# fg.net
KiCad netlist of a schematic drawn in EasyEDA Pro
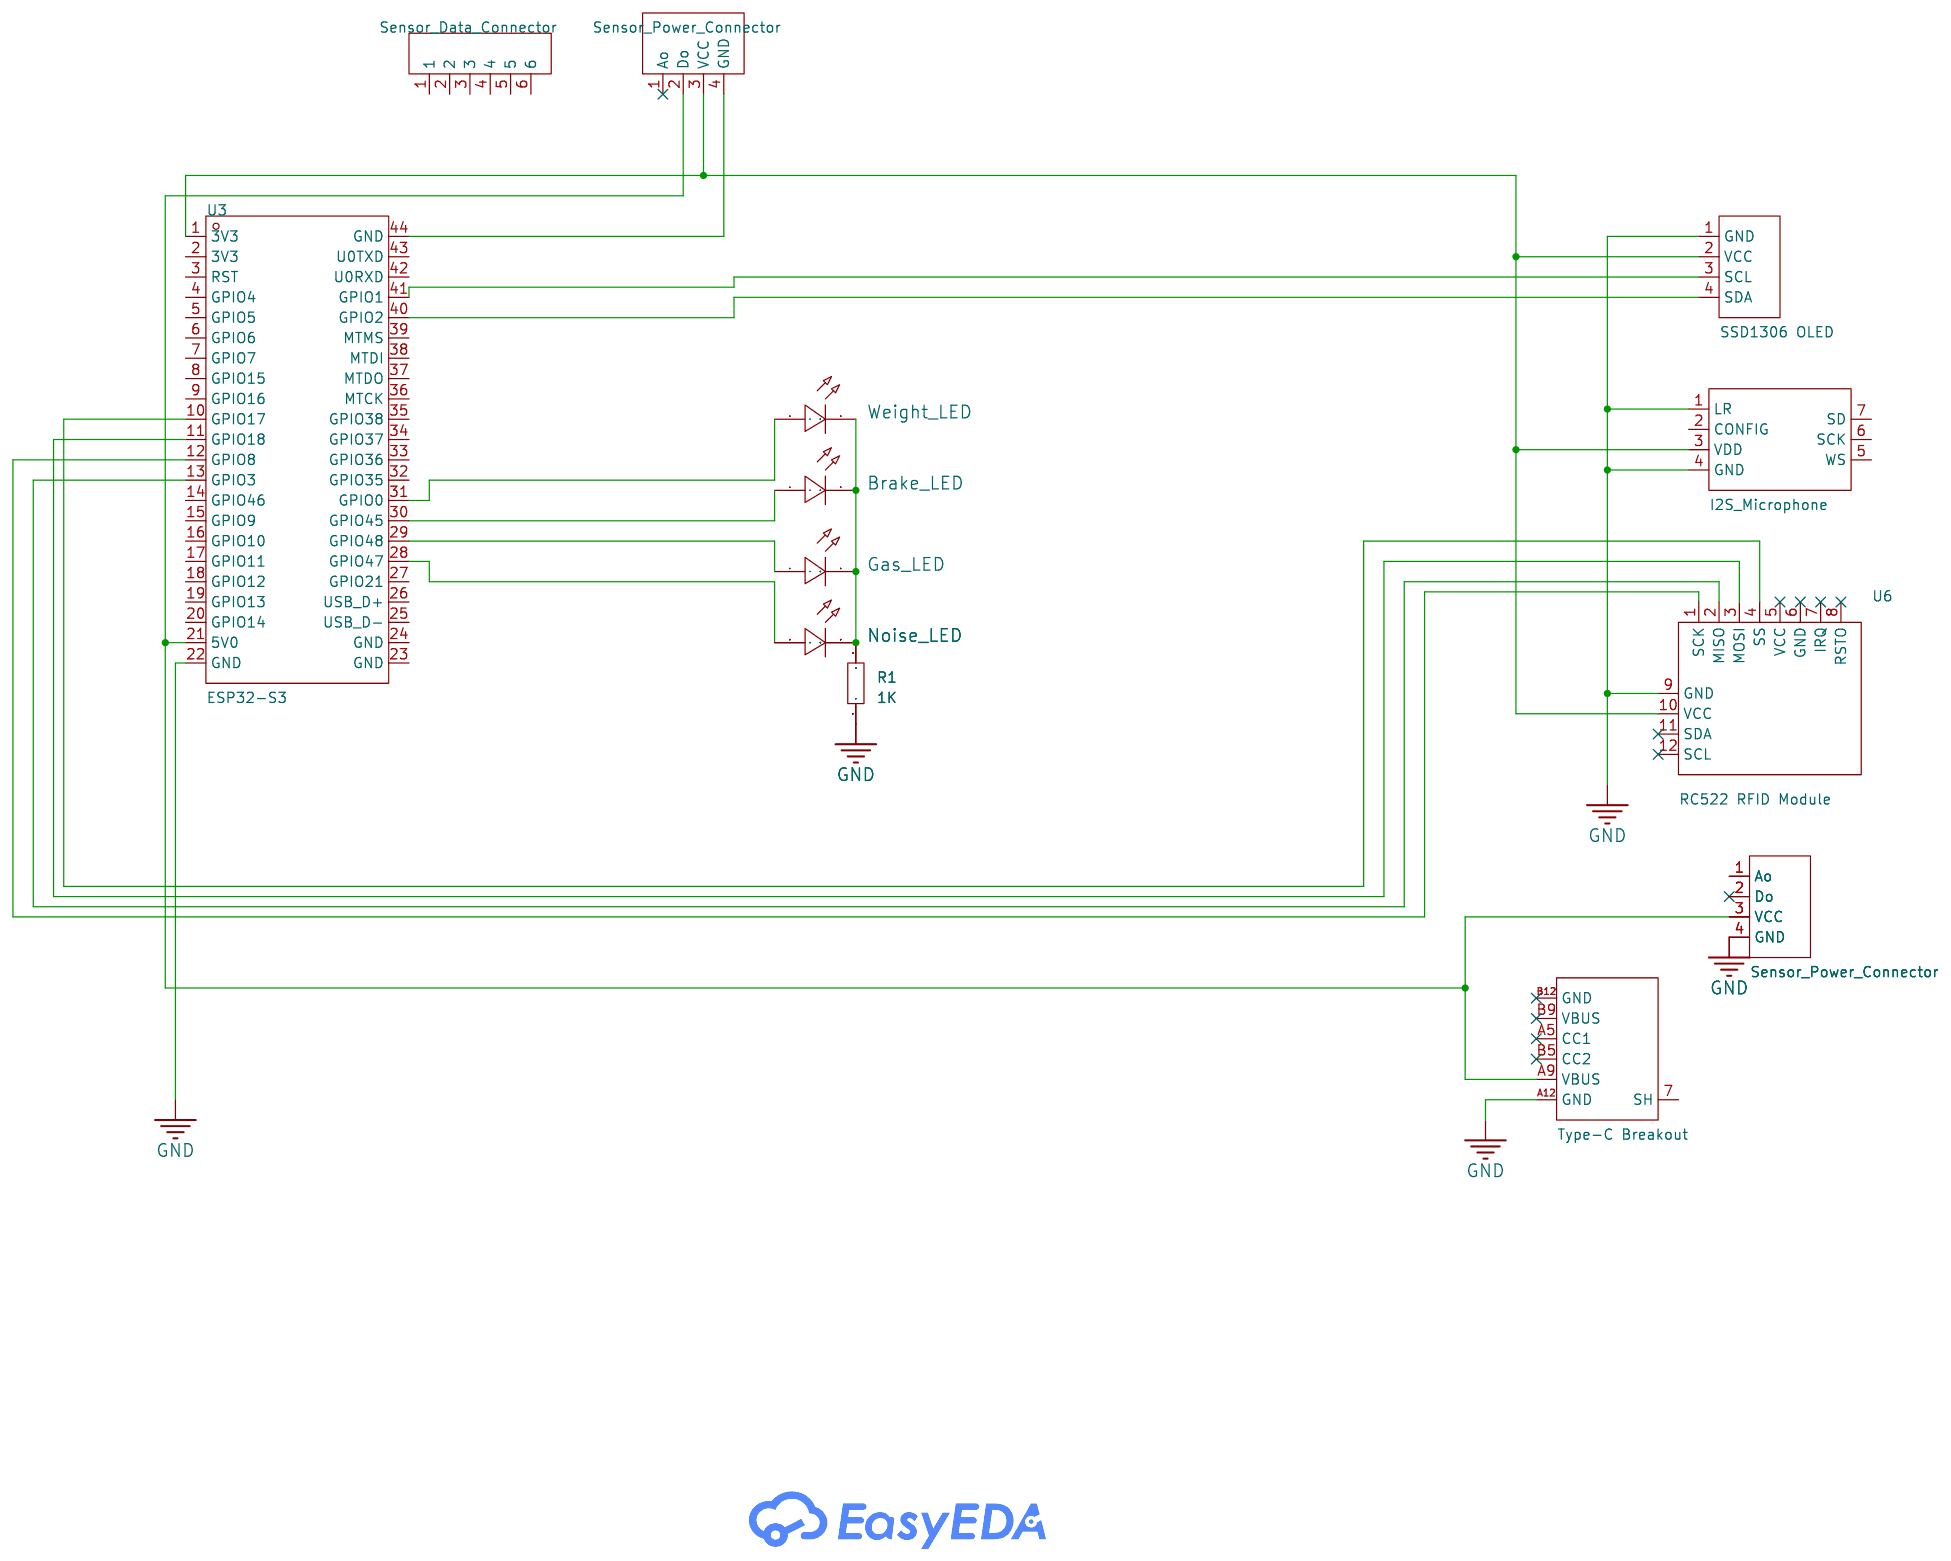
[diagram p0: schematic sheet]

(export (version "E")
  (design (tool "Eeschema 10.0.6"))
  (components
    (comp (ref "Brake_LED")
      (value "~")
      (footprint "easyedapro:LED0402-RD_YELLOW")
      (libsource (lib "easyedapro") (part "LED_R"))
    )
    (comp (ref "Display")
      (value "SSD1306 OLED")
      (footprint "easyedapro:OLED-TH_4P-L27.8-W27.3_MC096GW")
      (fields (field (name "Manufacturer Part") "MC096GW"))
      (libsource (lib "easyedapro") (part "MC096GW"))
    )
    (comp (ref "Gas_LED")
      (value "~")
      (footprint "easyedapro:LED0402-RD_YELLOW")
      (libsource (lib "easyedapro") (part "LED_R"))
    )
    (comp (ref "H1")
      (value "Sensor_Data_Connector")
      (footprint "easyedapro:HDR-TH_TW-06-01-T-S-150-085")
      (fields
        (field (name "Manufacturer Part") "TW-06-08-L-S-580-150")
        (field (name "Manufacturer") "SAMTEC")
      )
      (libsource (lib "easyedapro") (part "TW-06-08-L-S-580-150"))
    )
    (comp (ref "H2")
      (value "Sensor_Power_Connector")
      (footprint "easyedapro:HDR-TH_TW-04-06-T-S-433-120")
      (fields
        (field (name "Manufacturer Part") "TW-04-05-L-S-275-158")
        (field (name "Manufacturer") "SAMTEC")
      )
      (libsource (lib "easyedapro") (part "TW-04-05-L-S-275-158"))
    )
    (comp (ref "H3")
      (value "Sensor_Power_Connector")
      (footprint "easyedapro:HDR-TH_TW-04-06-T-S-433-120")
      (fields
        (field (name "Manufacturer Part") "TW-04-05-L-S-275-158")
        (field (name "Manufacturer") "SAMTEC")
      )
      (libsource (lib "easyedapro") (part "TW-04-05-L-S-275-158"))
    )
    (comp (ref "Noise_LED")
      (value "~")
      (footprint "easyedapro:LED0402-RD_YELLOW")
      (libsource (lib "easyedapro") (part "LED_R"))
    )
    (comp (ref "R1") (value "10K") (footprint "easyedapro:R0603") (libsource (lib "easyedapro") (part "Res")))
    (comp (ref "U3")
      (value "ESP32-S3")
      (footprint "easyedapro:COMM-TH_L63.3-W25.4-P2.54-LS22.86")
      (fields (field (name "Manufacturer Part") "ESP32-S3-DEV-KIT-N8R8"))
      (libsource (lib "easyedapro") (part "ESP32-S3-DEV-KIT-N8R8"))
    )
    (comp (ref "U5")
      (value "I2S_Microphone")
      (footprint "easyedapro:MIC-SMD_7P-L4.0-W3.0-P2.15-TL")
      (fields (field (name "Manufacturer Part") "DMM-4026-B-I2S-R") (field (name "Manufacturer") "PUIAUDIO"))
      (libsource (lib "easyedapro") (part "DMM-4026-B-I2S-R_C3171792"))
    )
    (comp (ref "U6")
      (value "RC522 RFID Module")
      (footprint "easyedapro:COMM-TH_L42.7-W40.4_PN532_NFC_RFID")
      (fields (field (name "Manufacturer Part") "PN532 NFC RFID Module v4"))
      (libsource (lib "easyedapro") (part "PN532 NFC RFID MODULE V4"))
    )
    (comp (ref "USB1")
      (value "Type-C Breakout")
      (footprint "easyedapro:USB-SMD_TYPE-C6P-ST")
      (fields (field (name "Manufacturer Part") "TCR51-65120601"))
      (libsource (lib "easyedapro") (part "TCR51-65120601"))
    )
    (comp (ref "Weight_LED")
      (value "~")
      (footprint "easyedapro:LED0402-RD_YELLOW")
      (libsource (lib "easyedapro") (part "LED_R"))
    )
  )
  (nets
    (net (code "1") (name "GND") (class "Default")
      (node (ref "Display") (pin "1") (pinfunction "GND_1") (pintype "unspecified"))
      (node (ref "H3") (pin "4") (pinfunction "GND_4") (pintype "unspecified"))
      (node (ref "R1") (pin "1") (pinfunction "1_1") (pintype "input"))
      (node (ref "U3") (pin "22") (pinfunction "GND_22") (pintype "unspecified"))
      (node (ref "U5") (pin "1") (pinfunction "LR_1") (pintype "unspecified"))
      (node (ref "U5") (pin "4") (pinfunction "GND_4") (pintype "unspecified"))
      (node (ref "U6") (pin "9") (pinfunction "GND_9") (pintype "unspecified"))
      (node (ref "USB1") (pin "A12") (pinfunction "GND_A12") (pintype "unspecified"))
    )
    (net (code "2") (name "Net-(Brake_LED-A)") (class "Default")
      (node (ref "Brake_LED") (pin "1") (pinfunction "A_1") (pintype "input"))
      (node (ref "U3") (pin "30") (pinfunction "GPIO45_30") (pintype "unspecified"))
    )
    (net (code "3") (name "Net-(Brake_LED-C)") (class "Default")
      (node (ref "Brake_LED") (pin "2") (pinfunction "C_2") (pintype "input"))
      (node (ref "Gas_LED") (pin "2") (pinfunction "C_2") (pintype "input"))
      (node (ref "Noise_LED") (pin "2") (pinfunction "C_2") (pintype "input"))
      (node (ref "R1") (pin "2") (pinfunction "2_2") (pintype "input"))
      (node (ref "Weight_LED") (pin "2") (pinfunction "C_2") (pintype "input"))
    )
    (net (code "4") (name "Net-(Display-SCL)") (class "Default")
      (node (ref "Display") (pin "3") (pinfunction "SCL_3") (pintype "unspecified"))
      (node (ref "U3") (pin "41") (pinfunction "GPIO1_41") (pintype "unspecified"))
    )
    (net (code "5") (name "Net-(Display-SDA)") (class "Default")
      (node (ref "Display") (pin "4") (pinfunction "SDA_4") (pintype "unspecified"))
      (node (ref "U3") (pin "40") (pinfunction "GPIO2_40") (pintype "unspecified"))
    )
    (net (code "6") (name "Net-(Display-VCC)") (class "Default")
      (node (ref "Display") (pin "2") (pinfunction "VCC_2") (pintype "unspecified"))
      (node (ref "H2") (pin "3") (pinfunction "VCC_3") (pintype "unspecified"))
      (node (ref "U3") (pin "1") (pinfunction "3V3_1") (pintype "unspecified"))
      (node (ref "U5") (pin "3") (pinfunction "VDD_3") (pintype "unspecified"))
      (node (ref "U6") (pin "10") (pinfunction "VCC_10") (pintype "unspecified"))
    )
    (net (code "7") (name "Net-(Gas_LED-A)") (class "Default")
      (node (ref "Gas_LED") (pin "1") (pinfunction "A_1") (pintype "input"))
      (node (ref "U3") (pin "29") (pinfunction "GPIO48_29") (pintype "unspecified"))
    )
    (net (code "8") (name "Net-(H2-Do)") (class "Default")
      (node (ref "H2") (pin "2") (pinfunction "Do_2") (pintype "unspecified"))
      (node (ref "H3") (pin "3") (pinfunction "VCC_3") (pintype "unspecified"))
      (node (ref "U3") (pin "21") (pinfunction "5V0_21") (pintype "unspecified"))
      (node (ref "USB1") (pin "A9") (pinfunction "VBUS_A9") (pintype "unspecified"))
    )
    (net (code "9") (name "Net-(H2-GND)") (class "Default")
      (node (ref "H2") (pin "4") (pinfunction "GND_4") (pintype "unspecified"))
      (node (ref "U3") (pin "44") (pinfunction "GND_44") (pintype "unspecified"))
    )
    (net (code "10") (name "Net-(Noise_LED-A)") (class "Default")
      (node (ref "Noise_LED") (pin "1") (pinfunction "A_1") (pintype "input"))
      (node (ref "U3") (pin "28") (pinfunction "GPIO47_28") (pintype "unspecified"))
    )
    (net (code "11") (name "Net-(U3-GPIO0)") (class "Default")
      (node (ref "U3") (pin "31") (pinfunction "GPIO0_31") (pintype "unspecified"))
      (node (ref "Weight_LED") (pin "1") (pinfunction "A_1") (pintype "input"))
    )
    (net (code "12") (name "Net-(U3-GPIO3)") (class "Default")
      (node (ref "U3") (pin "13") (pinfunction "GPIO3_13") (pintype "unspecified"))
      (node (ref "U6") (pin "2") (pinfunction "MISO_2") (pintype "unspecified"))
    )
    (net (code "13") (name "Net-(U3-GPIO8)") (class "Default")
      (node (ref "U3") (pin "12") (pinfunction "GPIO8_12") (pintype "unspecified"))
      (node (ref "U6") (pin "1") (pinfunction "SCK_1") (pintype "unspecified"))
    )
    (net (code "14") (name "Net-(U3-GPIO17)") (class "Default")
      (node (ref "U3") (pin "10") (pinfunction "GPIO17_10") (pintype "unspecified"))
      (node (ref "U6") (pin "4") (pinfunction "SS_4") (pintype "unspecified"))
    )
    (net (code "15") (name "Net-(U3-GPIO18)") (class "Default")
      (node (ref "U3") (pin "11") (pinfunction "GPIO18_11") (pintype "unspecified"))
      (node (ref "U6") (pin "3") (pinfunction "MOSI_3") (pintype "unspecified"))
    )
    (net (code "16") (name "unconnected-(H1-Pad1)") (class "Default")
      (node (ref "H1") (pin "1") (pinfunction "1_1") (pintype "unspecified"))
    )
    (net (code "17") (name "unconnected-(H1-Pad2)") (class "Default")
      (node (ref "H1") (pin "2") (pinfunction "2_2") (pintype "unspecified"))
    )
    (net (code "18") (name "unconnected-(H1-Pad3)") (class "Default")
      (node (ref "H1") (pin "3") (pinfunction "3_3") (pintype "unspecified"))
    )
    (net (code "19") (name "unconnected-(H1-Pad4)") (class "Default")
      (node (ref "H1") (pin "4") (pinfunction "4_4") (pintype "unspecified"))
    )
    (net (code "20") (name "unconnected-(H1-Pad5)") (class "Default")
      (node (ref "H1") (pin "5") (pinfunction "5_5") (pintype "unspecified"))
    )
    (net (code "21") (name "unconnected-(H1-Pad6)") (class "Default")
      (node (ref "H1") (pin "6") (pinfunction "6_6") (pintype "unspecified"))
    )
    (net (code "22") (name "unconnected-(H2-Ao-Pad1)") (class "Default")
      (node (ref "H2") (pin "1") (pinfunction "Ao_1") (pintype "unspecified+no_connect"))
    )
    (net (code "23") (name "unconnected-(H3-Ao-Pad1)") (class "Default")
      (node (ref "H3") (pin "1") (pinfunction "Ao_1") (pintype "unspecified"))
    )
    (net (code "24") (name "unconnected-(H3-Do-Pad2)") (class "Default")
      (node (ref "H3") (pin "2") (pinfunction "Do_2") (pintype "unspecified+no_connect"))
    )
    (net (code "25") (name "unconnected-(U3-3V3-Pad2)") (class "Default")
      (node (ref "U3") (pin "2") (pinfunction "3V3_2") (pintype "unspecified"))
    )
    (net (code "26") (name "unconnected-(U3-GND-Pad23)") (class "Default")
      (node (ref "U3") (pin "23") (pinfunction "GND_23") (pintype "unspecified"))
    )
    (net (code "27") (name "unconnected-(U3-GND-Pad24)") (class "Default")
      (node (ref "U3") (pin "24") (pinfunction "GND_24") (pintype "unspecified"))
    )
    (net (code "28") (name "unconnected-(U3-GPIO4-Pad4)") (class "Default")
      (node (ref "U3") (pin "4") (pinfunction "GPIO4_4") (pintype "unspecified"))
    )
    (net (code "29") (name "unconnected-(U3-GPIO5-Pad5)") (class "Default")
      (node (ref "U3") (pin "5") (pinfunction "GPIO5_5") (pintype "unspecified"))
    )
    (net (code "30") (name "unconnected-(U3-GPIO6-Pad6)") (class "Default")
      (node (ref "U3") (pin "6") (pinfunction "GPIO6_6") (pintype "unspecified"))
    )
    (net (code "31") (name "unconnected-(U3-GPIO7-Pad7)") (class "Default")
      (node (ref "U3") (pin "7") (pinfunction "GPIO7_7") (pintype "unspecified"))
    )
    (net (code "32") (name "unconnected-(U3-GPIO9-Pad15)") (class "Default")
      (node (ref "U3") (pin "15") (pinfunction "GPIO9_15") (pintype "unspecified"))
    )
    (net (code "33") (name "unconnected-(U3-GPIO10-Pad16)") (class "Default")
      (node (ref "U3") (pin "16") (pinfunction "GPIO10_16") (pintype "unspecified"))
    )
    (net (code "34") (name "unconnected-(U3-GPIO11-Pad17)") (class "Default")
      (node (ref "U3") (pin "17") (pinfunction "GPIO11_17") (pintype "unspecified"))
    )
    (net (code "35") (name "unconnected-(U3-GPIO12-Pad18)") (class "Default")
      (node (ref "U3") (pin "18") (pinfunction "GPIO12_18") (pintype "unspecified"))
    )
    (net (code "36") (name "unconnected-(U3-GPIO13-Pad19)") (class "Default")
      (node (ref "U3") (pin "19") (pinfunction "GPIO13_19") (pintype "unspecified"))
    )
    (net (code "37") (name "unconnected-(U3-GPIO14-Pad20)") (class "Default")
      (node (ref "U3") (pin "20") (pinfunction "GPIO14_20") (pintype "unspecified"))
    )
    (net (code "38") (name "unconnected-(U3-GPIO15-Pad8)") (class "Default")
      (node (ref "U3") (pin "8") (pinfunction "GPIO15_8") (pintype "unspecified"))
    )
    (net (code "39") (name "unconnected-(U3-GPIO16-Pad9)") (class "Default")
      (node (ref "U3") (pin "9") (pinfunction "GPIO16_9") (pintype "unspecified"))
    )
    (net (code "40") (name "unconnected-(U3-GPIO21-Pad27)") (class "Default")
      (node (ref "U3") (pin "27") (pinfunction "GPIO21_27") (pintype "unspecified"))
    )
    (net (code "41") (name "unconnected-(U3-GPIO35-Pad32)") (class "Default")
      (node (ref "U3") (pin "32") (pinfunction "GPIO35_32") (pintype "unspecified"))
    )
    (net (code "42") (name "unconnected-(U3-GPIO36-Pad33)") (class "Default")
      (node (ref "U3") (pin "33") (pinfunction "GPIO36_33") (pintype "unspecified"))
    )
    (net (code "43") (name "unconnected-(U3-GPIO37-Pad34)") (class "Default")
      (node (ref "U3") (pin "34") (pinfunction "GPIO37_34") (pintype "unspecified"))
    )
    (net (code "44") (name "unconnected-(U3-GPIO38-Pad35)") (class "Default")
      (node (ref "U3") (pin "35") (pinfunction "GPIO38_35") (pintype "unspecified"))
    )
    (net (code "45") (name "unconnected-(U3-GPIO46-Pad14)") (class "Default")
      (node (ref "U3") (pin "14") (pinfunction "GPIO46_14") (pintype "unspecified"))
    )
    (net (code "46") (name "unconnected-(U3-MTCK-Pad36)") (class "Default")
      (node (ref "U3") (pin "36") (pinfunction "MTCK_36") (pintype "unspecified"))
    )
    (net (code "47") (name "unconnected-(U3-MTDI-Pad38)") (class "Default")
      (node (ref "U3") (pin "38") (pinfunction "MTDI_38") (pintype "unspecified"))
    )
    (net (code "48") (name "unconnected-(U3-MTDO-Pad37)") (class "Default")
      (node (ref "U3") (pin "37") (pinfunction "MTDO_37") (pintype "unspecified"))
    )
    (net (code "49") (name "unconnected-(U3-MTMS-Pad39)") (class "Default")
      (node (ref "U3") (pin "39") (pinfunction "MTMS_39") (pintype "unspecified"))
    )
    (net (code "50") (name "unconnected-(U3-RST-Pad3)") (class "Default")
      (node (ref "U3") (pin "3") (pinfunction "RST_3") (pintype "unspecified"))
    )
    (net (code "51") (name "unconnected-(U3-U0RXD-Pad42)") (class "Default")
      (node (ref "U3") (pin "42") (pinfunction "U0RXD_42") (pintype "unspecified"))
    )
    (net (code "52") (name "unconnected-(U3-U0TXD-Pad43)") (class "Default")
      (node (ref "U3") (pin "43") (pinfunction "U0TXD_43") (pintype "unspecified"))
    )
    (net (code "53") (name "unconnected-(U3-USB_D+-Pad26)") (class "Default")
      (node (ref "U3") (pin "26") (pinfunction "USB_D+_26") (pintype "unspecified"))
    )
    (net (code "54") (name "unconnected-(U3-USB_D--Pad25)") (class "Default")
      (node (ref "U3") (pin "25") (pinfunction "USB_D-_25") (pintype "unspecified"))
    )
    (net (code "55") (name "unconnected-(U5-CONFIG-Pad2)") (class "Default")
      (node (ref "U5") (pin "2") (pinfunction "CONFIG_2") (pintype "unspecified"))
    )
    (net (code "56") (name "unconnected-(U5-SCK-Pad6)") (class "Default")
      (node (ref "U5") (pin "6") (pinfunction "SCK_6") (pintype "unspecified"))
    )
    (net (code "57") (name "unconnected-(U5-SD-Pad7)") (class "Default")
      (node (ref "U5") (pin "7") (pinfunction "SD_7") (pintype "unspecified"))
    )
    (net (code "58") (name "unconnected-(U5-WS-Pad5)") (class "Default")
      (node (ref "U5") (pin "5") (pinfunction "WS_5") (pintype "unspecified"))
    )
    (net (code "59") (name "unconnected-(U6-GND-Pad6)") (class "Default")
      (node (ref "U6") (pin "6") (pinfunction "GND_6") (pintype "unspecified+no_connect"))
    )
    (net (code "60") (name "unconnected-(U6-IRQ-Pad7)") (class "Default")
      (node (ref "U6") (pin "7") (pinfunction "IRQ_7") (pintype "unspecified+no_connect"))
    )
    (net (code "61") (name "unconnected-(U6-RSTO-Pad8)") (class "Default")
      (node (ref "U6") (pin "8") (pinfunction "RSTO_8") (pintype "unspecified+no_connect"))
    )
    (net (code "62") (name "unconnected-(U6-SCL-Pad12)") (class "Default")
      (node (ref "U6") (pin "12") (pinfunction "SCL_12") (pintype "unspecified+no_connect"))
    )
    (net (code "63") (name "unconnected-(U6-SDA-Pad11)") (class "Default")
      (node (ref "U6") (pin "11") (pinfunction "SDA_11") (pintype "unspecified+no_connect"))
    )
    (net (code "64") (name "unconnected-(U6-VCC-Pad5)") (class "Default")
      (node (ref "U6") (pin "5") (pinfunction "VCC_5") (pintype "unspecified+no_connect"))
    )
    (net (code "65") (name "unconnected-(USB1-CC1-PadA5)") (class "Default")
      (node (ref "USB1") (pin "A5") (pinfunction "CC1_A5") (pintype "unspecified+no_connect"))
    )
    (net (code "66") (name "unconnected-(USB1-CC2-PadB5)") (class "Default")
      (node (ref "USB1") (pin "B5") (pinfunction "CC2_B5") (pintype "unspecified+no_connect"))
    )
    (net (code "67") (name "unconnected-(USB1-GND-PadB12)") (class "Default")
      (node (ref "USB1") (pin "B12") (pinfunction "GND_B12") (pintype "unspecified+no_connect"))
    )
    (net (code "68") (name "unconnected-(USB1-SH-Pad7)") (class "Default")
      (node (ref "USB1") (pin "7") (pinfunction "SH_7") (pintype "unspecified"))
    )
    (net (code "69") (name "unconnected-(USB1-VBUS-PadB9)") (class "Default")
      (node (ref "USB1") (pin "B9") (pinfunction "VBUS_B9") (pintype "unspecified+no_connect"))
    )
  )
)
